# audio.net
KiCad netlist of a schematic drawn in Altium Designer
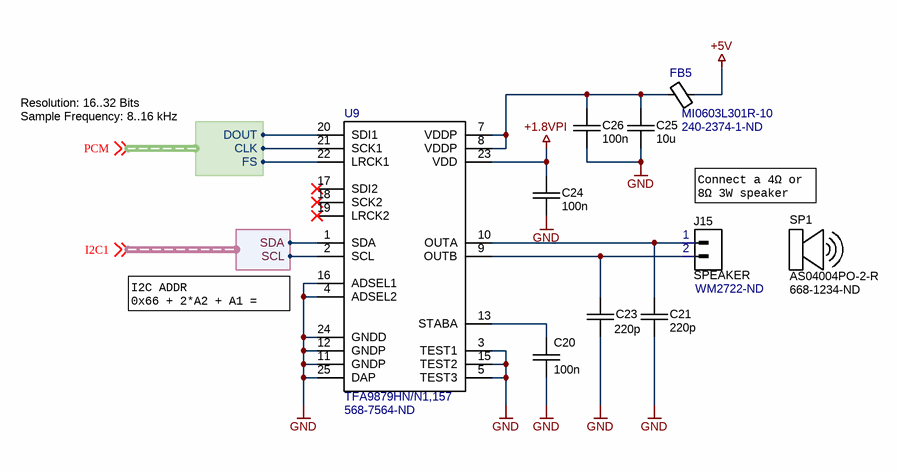
[diagram p0: audio.SchDoc]

(export (version "E")
  (design (tool "Eeschema 10.0.6"))
  (components
    (comp (ref "C20")
      (value "100n")
      (footprint "SM/C0603")
      (description "Chip Capacitor")
      (fields (field (name "VOLTAGE") "16V"))
      (libsource (lib "kalios") (part "C"))
    )
    (comp (ref "C21")
      (value "220p")
      (footprint "SM/C0603")
      (description "Chip Capacitor")
      (fields (field (name "VOLTAGE") "16V"))
      (libsource (lib "kalios") (part "C"))
    )
    (comp (ref "C23")
      (value "220p")
      (footprint "SM/C0603")
      (description "Chip Capacitor")
      (fields (field (name "VOLTAGE") "16V"))
      (libsource (lib "kalios") (part "C"))
    )
    (comp (ref "C24")
      (value "100n")
      (footprint "SM/C0603")
      (description "Chip Capacitor")
      (fields (field (name "VOLTAGE") "16V"))
      (libsource (lib "kalios") (part "C"))
    )
    (comp (ref "C25")
      (value "10u")
      (footprint "SM/C0805")
      (description "CAP CER 10UF 10V X5R 0805")
      (libsource (lib "kalios") (part "C"))
    )
    (comp (ref "C26")
      (value "100n")
      (footprint "SM/C0603")
      (description "Chip Capacitor")
      (fields (field (name "VOLTAGE") "16V"))
      (libsource (lib "kalios") (part "C"))
    )
    (comp (ref "FB5")
      (value "MI0603L301R-10")
      (footprint "SM/L0603")
      (fields (field (name "SUPPLIER PART NUMBER 1") "240-2374-1-ND"))
      (libsource (lib "kalios") (part "FB0603"))
    )
    (comp (ref "J15")
      (value "SPEAKER")
      (footprint "CONN/HEADER/2.54mm/2POS")
      (fields (field (name "SUPPLIER PART NUMBER 1") "WM2722-ND"))
      (libsource (lib "kalios") (part "CONN 2 MALE"))
    )
    (comp (ref "SP1")
      (value "AS04004PO-2-R")
      (description "SPEAKER 4OHM 3W TOP PORT 82DB")
      (fields (field (name "SUPPLIER PART NUMBER 1") "668-1234-ND"))
      (libsource (lib "kalios") (part "SPEAKER/3W"))
    )
    (comp (ref "U9")
      (value "TFA9879HN/N1,157")
      (footprint "QFN50P260X260X100-25N")
      (description "IC AMP CLSS D MONO 2.75W 24HVQFN")
      (fields (field (name "SUPPLIER PART NUMBER 1") "568-7564-ND"))
      (libsource (lib "kalios") (part "TFA9879"))
    )
  )
  (nets
    (net (code "1") (name "+1.8VPI") (class "Default")
      (node (ref "C24") (pin "1") (pintype "passive"))
      (node (ref "U9") (pin "23") (pinfunction "VDD_23") (pintype "passive"))
    )
    (net (code "2") (name "+5V") (class "Default")
      (node (ref "FB5") (pin "1") (pinfunction "1_1") (pintype "passive"))
    )
    (net (code "3") (name "/CLK") (class "Default")
      (node (ref "U9") (pin "21") (pinfunction "SCK1_21") (pintype "passive"))
    )
    (net (code "4") (name "/DOUT") (class "Default")
      (node (ref "U9") (pin "20") (pinfunction "SDI1_20") (pintype "passive"))
    )
    (net (code "5") (name "/FS") (class "Default")
      (node (ref "U9") (pin "22") (pinfunction "LRCK1_22") (pintype "passive"))
    )
    (net (code "6") (name "/SCL") (class "Default")
      (node (ref "U9") (pin "2") (pinfunction "SCL_2") (pintype "passive"))
    )
    (net (code "7") (name "/SDA") (class "Default")
      (node (ref "U9") (pin "1") (pinfunction "SDA_1") (pintype "passive"))
    )
    (net (code "8") (name "GND") (class "Default")
      (node (ref "C20") (pin "2") (pintype "passive"))
      (node (ref "C21") (pin "2") (pintype "passive"))
      (node (ref "C23") (pin "2") (pintype "passive"))
      (node (ref "C24") (pin "2") (pintype "passive"))
      (node (ref "C25") (pin "2") (pintype "passive"))
      (node (ref "C26") (pin "2") (pintype "passive"))
      (node (ref "U9") (pin "11") (pinfunction "GNDP_11") (pintype "passive"))
      (node (ref "U9") (pin "12") (pinfunction "GNDP_12") (pintype "passive"))
      (node (ref "U9") (pin "15") (pinfunction "TEST2_15") (pintype "passive"))
      (node (ref "U9") (pin "16") (pinfunction "ADSEL1_16") (pintype "passive"))
      (node (ref "U9") (pin "24") (pinfunction "GNDD_24") (pintype "passive"))
      (node (ref "U9") (pin "25") (pinfunction "DAP_25") (pintype "passive"))
      (node (ref "U9") (pin "3") (pinfunction "TEST1_3") (pintype "passive"))
      (node (ref "U9") (pin "4") (pinfunction "ADSEL2_4") (pintype "passive"))
      (node (ref "U9") (pin "5") (pinfunction "TEST3_5") (pintype "passive"))
    )
    (net (code "10") (name "Net-(C25-Pad1)") (class "Default")
      (node (ref "C25") (pin "1") (pintype "passive"))
      (node (ref "C26") (pin "1") (pintype "passive"))
      (node (ref "FB5") (pin "2") (pinfunction "2_2") (pintype "passive"))
      (node (ref "U9") (pin "7") (pinfunction "VDDP_7") (pintype "passive"))
      (node (ref "U9") (pin "8") (pinfunction "VDDP_8") (pintype "passive"))
    )
    (net (code "11") (name "Net-(U9-OUTA)") (class "Default")
      (node (ref "C21") (pin "1") (pintype "passive"))
      (node (ref "J15") (pin "1") (pinfunction "1_1") (pintype "passive"))
      (node (ref "U9") (pin "10") (pinfunction "OUTA_10") (pintype "passive"))
    )
    (net (code "12") (name "Net-(U9-OUTB)") (class "Default")
      (node (ref "C23") (pin "1") (pintype "passive"))
      (node (ref "J15") (pin "2") (pinfunction "2_2") (pintype "passive"))
      (node (ref "U9") (pin "9") (pinfunction "OUTB_9") (pintype "passive"))
    )
    (net (code "13") (name "Net-(U9-STABA)") (class "Default")
      (node (ref "C20") (pin "1") (pintype "passive"))
      (node (ref "U9") (pin "13") (pinfunction "STABA_13") (pintype "passive"))
    )
    (net (code "15") (name "unconnected-(U9-LRCK2-Pad19)") (class "Default")
      (node (ref "U9") (pin "19") (pinfunction "LRCK2_19") (pintype "passive+no_connect"))
    )
    (net (code "16") (name "unconnected-(U9-SCK2-Pad18)") (class "Default")
      (node (ref "U9") (pin "18") (pinfunction "SCK2_18") (pintype "passive+no_connect"))
    )
    (net (code "17") (name "unconnected-(U9-SDI2-Pad17)") (class "Default")
      (node (ref "U9") (pin "17") (pinfunction "SDI2_17") (pintype "passive+no_connect"))
    )
  )
)
